# demo.net
KiCad netlist of a schematic drawn in EasyEDA Pro
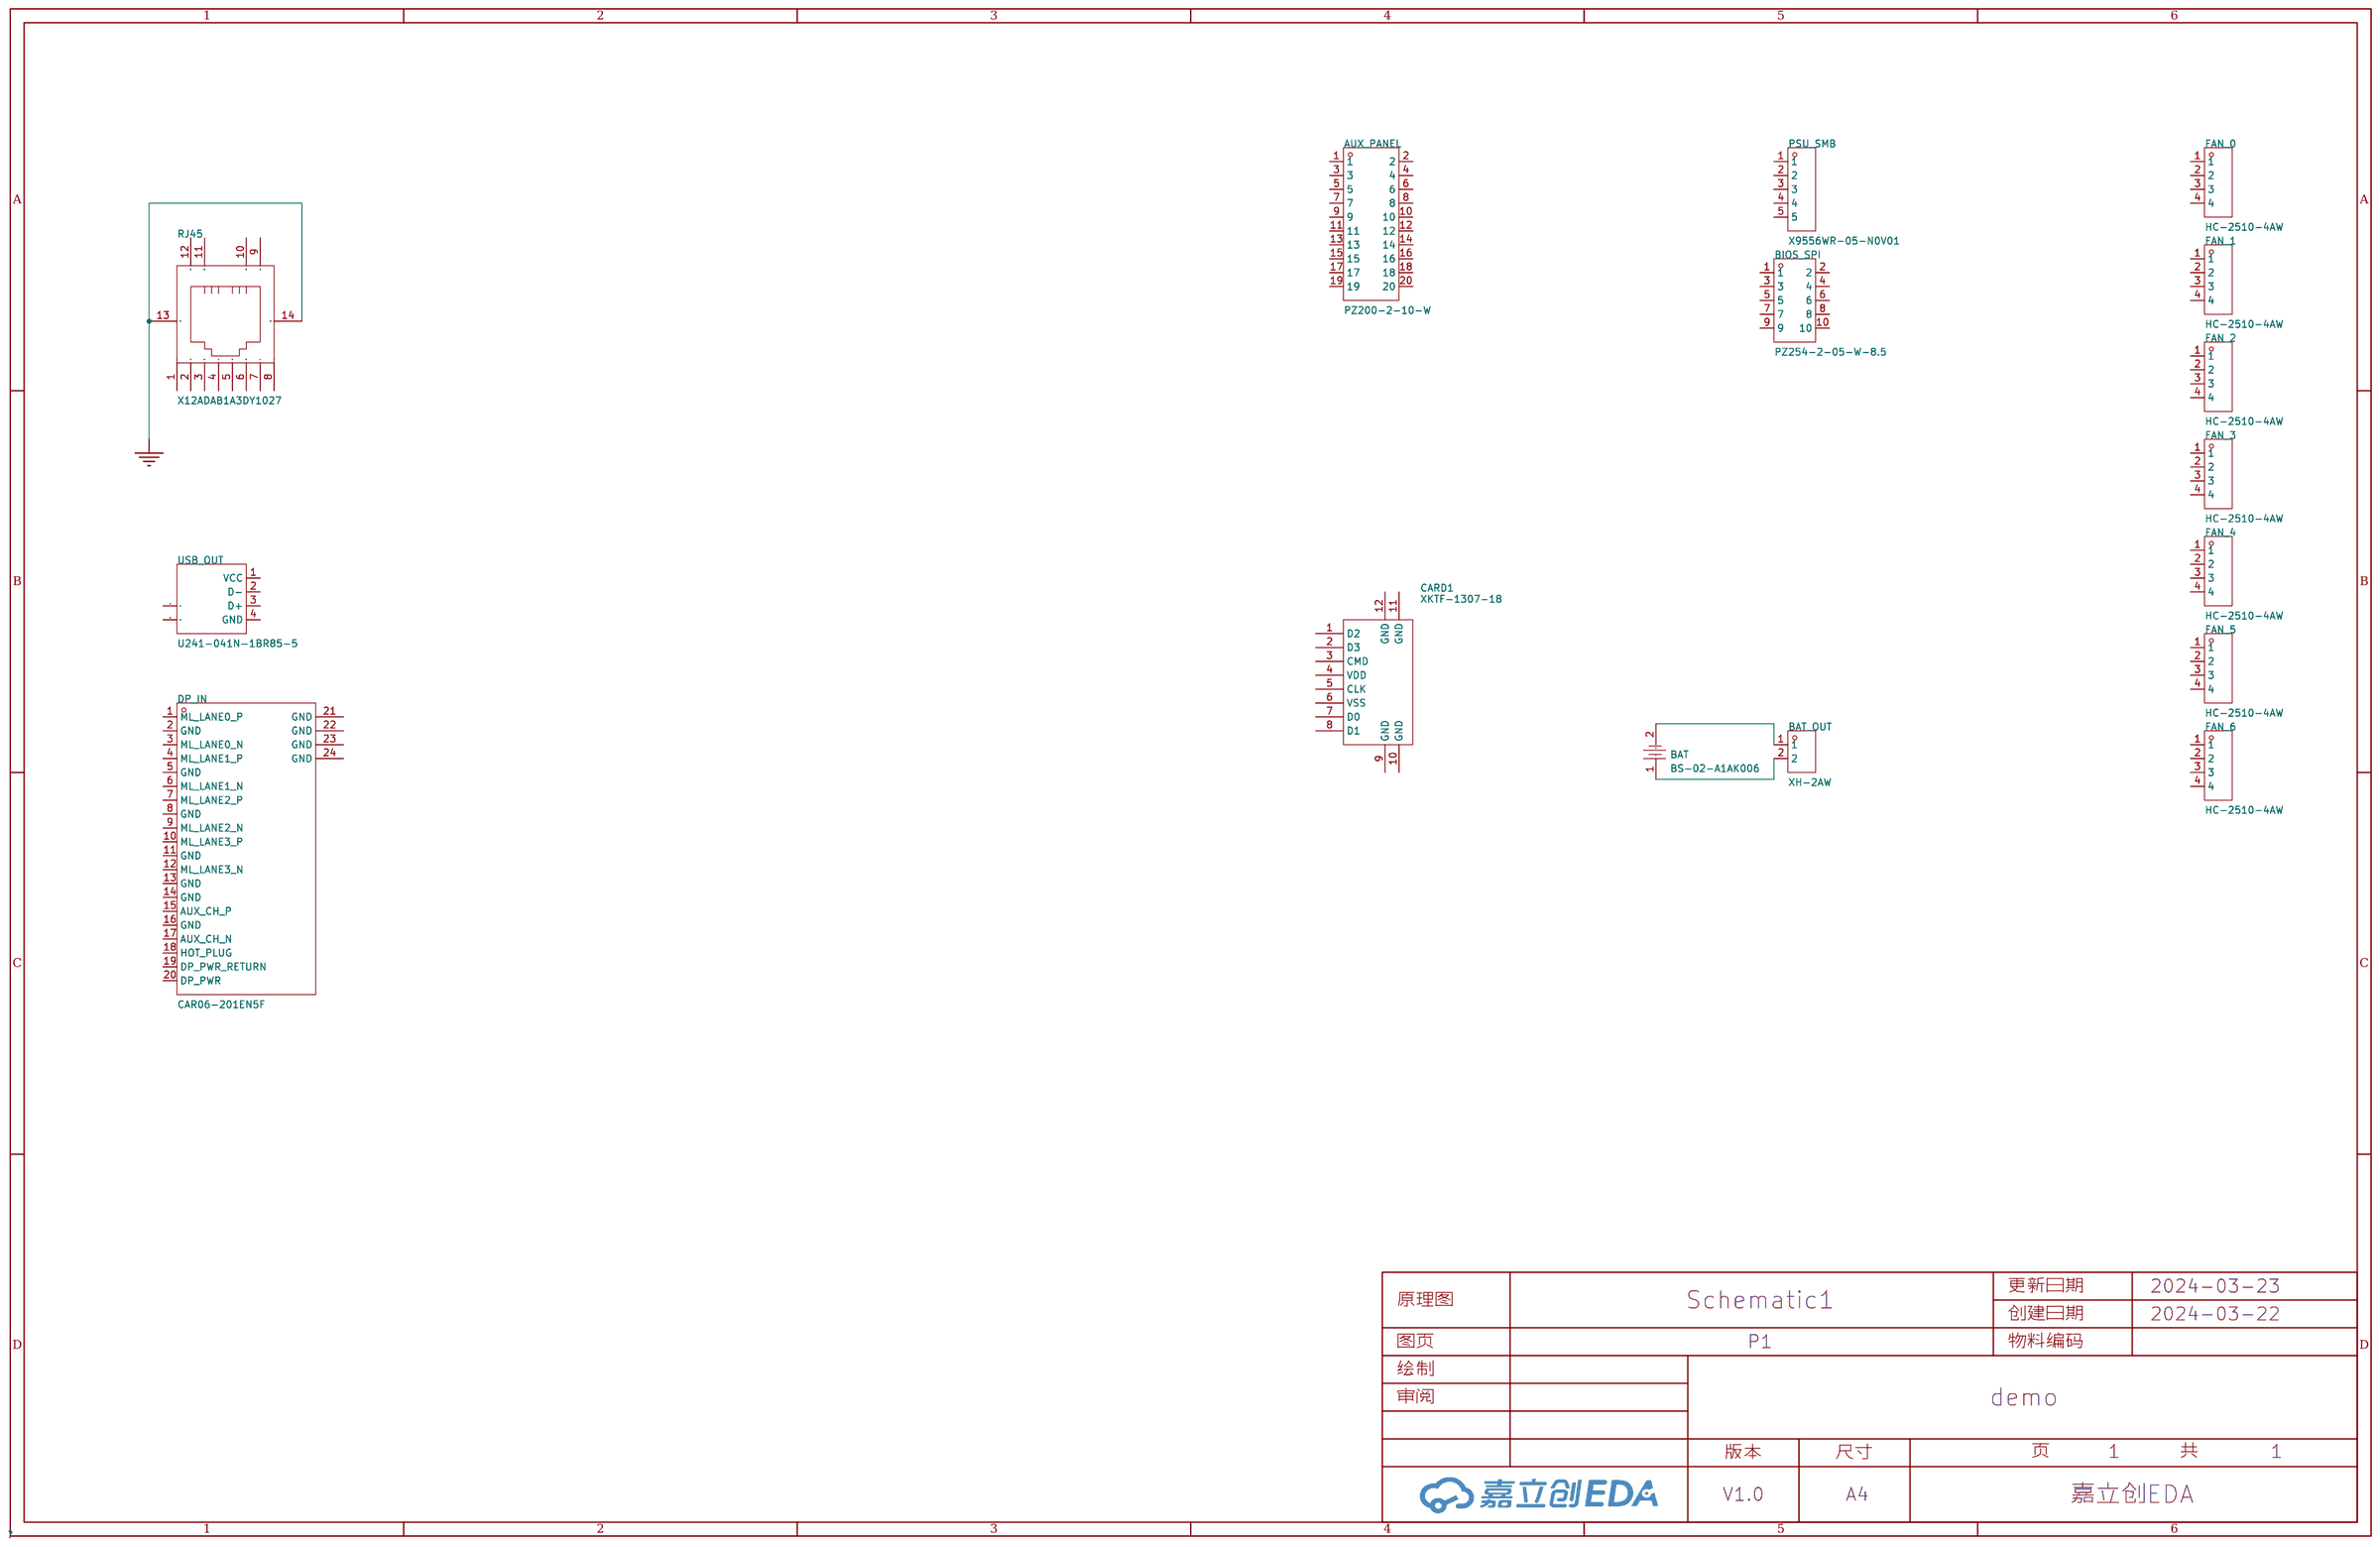
[diagram p0: schematic sheet]

(export (version "E")
  (design (tool "Eeschema 10.0.6"))
  (components
    (comp (ref "AUX_PANEL")
      (value "PZ200-2-10-W")
      (footprint "easyedapro:HDR-TH_20P-P2.00-H-M-R2-C10-S2.00-W9.4")
      (fields (field (name "Manufacturer") "HCTL(华灿天禄)"))
      (libsource (lib "easyedapro") (part "PZ200-2-10-W"))
    )
    (comp (ref "BAT")
      (value "BS-02-A1AK006")
      (footprint "easyedapro:BAT-TH_BS-02-A1AK006")
      (description "连接器类型:电池底座;适用电池规格:CR2032;触点电镀:锡;工作温度范围:-25°C~+85°C;")
      (fields (field (name "Manufacturer") "MYOUNG(美阳)"))
      (libsource (lib "easyedapro") (part "BS-02-A1AK006"))
    )
    (comp (ref "BAT_OUT")
      (value "XH-2AW")
      (footprint "easyedapro:CONN-TH_XH-2AW_C2908611")
      (fields (field (name "Manufacturer") "HCTL(华灿天禄)"))
      (libsource (lib "easyedapro") (part "XH-2AW_C2908611"))
    )
    (comp (ref "BIOS_SPI")
      (value "PZ254-2-05-W-8.5")
      (footprint "easyedapro:HDR-TH_10P-P2.54-H-M-R2-C5-S2.54-N")
      (fields (field (name "Manufacturer") "HCTL(华灿天禄)"))
      (libsource (lib "easyedapro") (part "PZ254-2-05-W-8.5"))
    )
    (comp (ref "CARD1")
      (value "XKTF-1307-18")
      (footprint "easyedapro:TF-SMD_XKTF-1307-18")
      (fields (field (name "Manufacturer") "XKB Connectivity(中国星坤)"))
      (libsource (lib "easyedapro") (part "XKTF-1307-18"))
    )
    (comp (ref "DP_IN")
      (value "CAR06-201EN5F")
      (footprint "easyedapro:DP-SMD_CAR06-201EN5F")
      (description "连接器类型:DisplayPort;公母:母;总PIN位数:20P;安装方式:卧贴;排数:1;额定电流:500mA;工作温度范围:-25°C~+85°C;")
      (fields (field (name "Manufacturer") "XKB Connectivity(中国星坤)"))
      (libsource (lib "easyedapro") (part "CAR06-201EN5F"))
    )
    (comp (ref "FAN_0")
      (value "HC-2510-4AW")
      (footprint "easyedapro:CONN-TH_4P-P2.54_HCTL_HC-2510-4AW")
      (fields (field (name "Manufacturer") "HCTL(华灿天禄)"))
      (libsource (lib "easyedapro") (part "HC-2510-4AW"))
    )
    (comp (ref "FAN_1")
      (value "HC-2510-4AW")
      (footprint "easyedapro:CONN-TH_4P-P2.54_HCTL_HC-2510-4AW")
      (fields (field (name "Manufacturer") "HCTL(华灿天禄)"))
      (libsource (lib "easyedapro") (part "HC-2510-4AW"))
    )
    (comp (ref "FAN_2")
      (value "HC-2510-4AW")
      (footprint "easyedapro:CONN-TH_4P-P2.54_HCTL_HC-2510-4AW")
      (fields (field (name "Manufacturer") "HCTL(华灿天禄)"))
      (libsource (lib "easyedapro") (part "HC-2510-4AW"))
    )
    (comp (ref "FAN_3")
      (value "HC-2510-4AW")
      (footprint "easyedapro:CONN-TH_4P-P2.54_HCTL_HC-2510-4AW")
      (fields (field (name "Manufacturer") "HCTL(华灿天禄)"))
      (libsource (lib "easyedapro") (part "HC-2510-4AW"))
    )
    (comp (ref "FAN_4")
      (value "HC-2510-4AW")
      (footprint "easyedapro:CONN-TH_4P-P2.54_HCTL_HC-2510-4AW")
      (fields (field (name "Manufacturer") "HCTL(华灿天禄)"))
      (libsource (lib "easyedapro") (part "HC-2510-4AW"))
    )
    (comp (ref "FAN_5")
      (value "HC-2510-4AW")
      (footprint "easyedapro:CONN-TH_4P-P2.54_HCTL_HC-2510-4AW")
      (fields (field (name "Manufacturer") "HCTL(华灿天禄)"))
      (libsource (lib "easyedapro") (part "HC-2510-4AW"))
    )
    (comp (ref "FAN_6")
      (value "HC-2510-4AW")
      (footprint "easyedapro:CONN-TH_4P-P2.54_HCTL_HC-2510-4AW")
      (fields (field (name "Manufacturer") "HCTL(华灿天禄)"))
      (libsource (lib "easyedapro") (part "HC-2510-4AW"))
    )
    (comp (ref "PSU_SMB")
      (value "X9556WR-05-N0V01")
      (footprint "easyedapro:CONN-TH_5P-P2.54_X9556WR-05-N0V01")
      (fields (field (name "Manufacturer") "XKB Connectivity(中国星坤)"))
      (libsource (lib "easyedapro") (part "X9556WR-05-N0V01"))
    )
    (comp (ref "RJ45")
      (value "X12ADAB1A3DY1027")
      (footprint "easyedapro:RJ45-TH_XKB_X12ADAB1A3DY1027")
      (fields (field (name "Manufacturer") "XKB Connectivity(中国星坤)"))
      (libsource (lib "easyedapro") (part "X12ADAB1A3DY1027"))
    )
    (comp (ref "USB_OUT")
      (value "U241-041N-1BR85-5")
      (footprint "easyedapro:USB-B-TH_U241-041N-1BR85-1")
      (fields (field (name "Manufacturer") "XKB Connectivity(中国星坤)"))
      (libsource (lib "easyedapro") (part "U241-041N-1BR85-5"))
    )
  )
  (nets
    (net (code "1") (name "GND") (class "Default")
      (node (ref "RJ45") (pin "13") (pinfunction "GND_13") (pintype "unspecified"))
      (node (ref "RJ45") (pin "14") (pinfunction "GND_14") (pintype "unspecified"))
    )
    (net (code "2") (name "Net-(BAT-Pad1)") (class "Default")
      (node (ref "BAT") (pin "1") (pinfunction "1_1") (pintype "input"))
      (node (ref "BAT_OUT") (pin "2") (pinfunction "2_2") (pintype "unspecified"))
    )
    (net (code "3") (name "Net-(BAT-Pad2)") (class "Default")
      (node (ref "BAT") (pin "2") (pinfunction "2_2") (pintype "input"))
      (node (ref "BAT_OUT") (pin "1") (pinfunction "1_1") (pintype "unspecified"))
    )
    (net (code "4") (name "unconnected-(AUX_PANEL-Pad1)") (class "Default")
      (node (ref "AUX_PANEL") (pin "1") (pinfunction "1_1") (pintype "unspecified"))
    )
    (net (code "5") (name "unconnected-(AUX_PANEL-Pad2)") (class "Default")
      (node (ref "AUX_PANEL") (pin "2") (pinfunction "2_2") (pintype "unspecified"))
    )
    (net (code "6") (name "unconnected-(AUX_PANEL-Pad3)") (class "Default")
      (node (ref "AUX_PANEL") (pin "3") (pinfunction "3_3") (pintype "unspecified"))
    )
    (net (code "7") (name "unconnected-(AUX_PANEL-Pad4)") (class "Default")
      (node (ref "AUX_PANEL") (pin "4") (pinfunction "4_4") (pintype "unspecified"))
    )
    (net (code "8") (name "unconnected-(AUX_PANEL-Pad5)") (class "Default")
      (node (ref "AUX_PANEL") (pin "5") (pinfunction "5_5") (pintype "unspecified"))
    )
    (net (code "9") (name "unconnected-(AUX_PANEL-Pad6)") (class "Default")
      (node (ref "AUX_PANEL") (pin "6") (pinfunction "6_6") (pintype "unspecified"))
    )
    (net (code "10") (name "unconnected-(AUX_PANEL-Pad7)") (class "Default")
      (node (ref "AUX_PANEL") (pin "7") (pinfunction "7_7") (pintype "unspecified"))
    )
    (net (code "11") (name "unconnected-(AUX_PANEL-Pad8)") (class "Default")
      (node (ref "AUX_PANEL") (pin "8") (pinfunction "8_8") (pintype "unspecified"))
    )
    (net (code "12") (name "unconnected-(AUX_PANEL-Pad9)") (class "Default")
      (node (ref "AUX_PANEL") (pin "9") (pinfunction "9_9") (pintype "unspecified"))
    )
    (net (code "13") (name "unconnected-(AUX_PANEL-Pad10)") (class "Default")
      (node (ref "AUX_PANEL") (pin "10") (pinfunction "10_10") (pintype "unspecified"))
    )
    (net (code "14") (name "unconnected-(AUX_PANEL-Pad11)") (class "Default")
      (node (ref "AUX_PANEL") (pin "11") (pinfunction "11_11") (pintype "unspecified"))
    )
    (net (code "15") (name "unconnected-(AUX_PANEL-Pad12)") (class "Default")
      (node (ref "AUX_PANEL") (pin "12") (pinfunction "12_12") (pintype "unspecified"))
    )
    (net (code "16") (name "unconnected-(AUX_PANEL-Pad13)") (class "Default")
      (node (ref "AUX_PANEL") (pin "13") (pinfunction "13_13") (pintype "unspecified"))
    )
    (net (code "17") (name "unconnected-(AUX_PANEL-Pad14)") (class "Default")
      (node (ref "AUX_PANEL") (pin "14") (pinfunction "14_14") (pintype "unspecified"))
    )
    (net (code "18") (name "unconnected-(AUX_PANEL-Pad15)") (class "Default")
      (node (ref "AUX_PANEL") (pin "15") (pinfunction "15_15") (pintype "unspecified"))
    )
    (net (code "19") (name "unconnected-(AUX_PANEL-Pad16)") (class "Default")
      (node (ref "AUX_PANEL") (pin "16") (pinfunction "16_16") (pintype "unspecified"))
    )
    (net (code "20") (name "unconnected-(AUX_PANEL-Pad17)") (class "Default")
      (node (ref "AUX_PANEL") (pin "17") (pinfunction "17_17") (pintype "unspecified"))
    )
    (net (code "21") (name "unconnected-(AUX_PANEL-Pad18)") (class "Default")
      (node (ref "AUX_PANEL") (pin "18") (pinfunction "18_18") (pintype "unspecified"))
    )
    (net (code "22") (name "unconnected-(AUX_PANEL-Pad19)") (class "Default")
      (node (ref "AUX_PANEL") (pin "19") (pinfunction "19_19") (pintype "unspecified"))
    )
    (net (code "23") (name "unconnected-(AUX_PANEL-Pad20)") (class "Default")
      (node (ref "AUX_PANEL") (pin "20") (pinfunction "20_20") (pintype "unspecified"))
    )
    (net (code "24") (name "unconnected-(BIOS_SPI-Pad1)") (class "Default")
      (node (ref "BIOS_SPI") (pin "1") (pinfunction "1_1") (pintype "unspecified"))
    )
    (net (code "25") (name "unconnected-(BIOS_SPI-Pad2)") (class "Default")
      (node (ref "BIOS_SPI") (pin "2") (pinfunction "2_2") (pintype "unspecified"))
    )
    (net (code "26") (name "unconnected-(BIOS_SPI-Pad3)") (class "Default")
      (node (ref "BIOS_SPI") (pin "3") (pinfunction "3_3") (pintype "unspecified"))
    )
    (net (code "27") (name "unconnected-(BIOS_SPI-Pad4)") (class "Default")
      (node (ref "BIOS_SPI") (pin "4") (pinfunction "4_4") (pintype "unspecified"))
    )
    (net (code "28") (name "unconnected-(BIOS_SPI-Pad5)") (class "Default")
      (node (ref "BIOS_SPI") (pin "5") (pinfunction "5_5") (pintype "unspecified"))
    )
    (net (code "29") (name "unconnected-(BIOS_SPI-Pad6)") (class "Default")
      (node (ref "BIOS_SPI") (pin "6") (pinfunction "6_6") (pintype "unspecified"))
    )
    (net (code "30") (name "unconnected-(BIOS_SPI-Pad7)") (class "Default")
      (node (ref "BIOS_SPI") (pin "7") (pinfunction "7_7") (pintype "unspecified"))
    )
    (net (code "31") (name "unconnected-(BIOS_SPI-Pad8)") (class "Default")
      (node (ref "BIOS_SPI") (pin "8") (pinfunction "8_8") (pintype "unspecified"))
    )
    (net (code "32") (name "unconnected-(BIOS_SPI-Pad9)") (class "Default")
      (node (ref "BIOS_SPI") (pin "9") (pinfunction "9_9") (pintype "unspecified"))
    )
    (net (code "33") (name "unconnected-(BIOS_SPI-Pad10)") (class "Default")
      (node (ref "BIOS_SPI") (pin "10") (pinfunction "10_10") (pintype "unspecified"))
    )
    (net (code "34") (name "unconnected-(CARD1-CLK-Pad5)") (class "Default")
      (node (ref "CARD1") (pin "5") (pinfunction "CLK_5") (pintype "input"))
    )
    (net (code "35") (name "unconnected-(CARD1-CMD-Pad3)") (class "Default")
      (node (ref "CARD1") (pin "3") (pinfunction "CMD_3") (pintype "input"))
    )
    (net (code "36") (name "unconnected-(CARD1-D0-Pad7)") (class "Default")
      (node (ref "CARD1") (pin "7") (pinfunction "D0_7") (pintype "input"))
    )
    (net (code "37") (name "unconnected-(CARD1-D1-Pad8)") (class "Default")
      (node (ref "CARD1") (pin "8") (pinfunction "D1_8") (pintype "input"))
    )
    (net (code "38") (name "unconnected-(CARD1-D2-Pad1)") (class "Default")
      (node (ref "CARD1") (pin "1") (pinfunction "D2_1") (pintype "input"))
    )
    (net (code "39") (name "unconnected-(CARD1-D3-Pad2)") (class "Default")
      (node (ref "CARD1") (pin "2") (pinfunction "D3_2") (pintype "input"))
    )
    (net (code "40") (name "unconnected-(CARD1-GND-Pad9)") (class "Default")
      (node (ref "CARD1") (pin "9") (pinfunction "GND_9") (pintype "input"))
    )
    (net (code "41") (name "unconnected-(CARD1-GND-Pad10)") (class "Default")
      (node (ref "CARD1") (pin "10") (pinfunction "GND_10") (pintype "input"))
    )
    (net (code "42") (name "unconnected-(CARD1-GND-Pad11)") (class "Default")
      (node (ref "CARD1") (pin "11") (pinfunction "GND_11") (pintype "input"))
    )
    (net (code "43") (name "unconnected-(CARD1-GND-Pad12)") (class "Default")
      (node (ref "CARD1") (pin "12") (pinfunction "GND_12") (pintype "input"))
    )
    (net (code "44") (name "unconnected-(CARD1-VDD-Pad4)") (class "Default")
      (node (ref "CARD1") (pin "4") (pinfunction "VDD_4") (pintype "input"))
    )
    (net (code "45") (name "unconnected-(CARD1-VSS-Pad6)") (class "Default")
      (node (ref "CARD1") (pin "6") (pinfunction "VSS_6") (pintype "input"))
    )
    (net (code "46") (name "unconnected-(DP_IN-AUX_CH_N-Pad17)") (class "Default")
      (node (ref "DP_IN") (pin "17") (pinfunction "AUX_CH_N_17") (pintype "unspecified"))
    )
    (net (code "47") (name "unconnected-(DP_IN-AUX_CH_P-Pad15)") (class "Default")
      (node (ref "DP_IN") (pin "15") (pinfunction "AUX_CH_P_15") (pintype "unspecified"))
    )
    (net (code "48") (name "unconnected-(DP_IN-DP_PWR-Pad20)") (class "Default")
      (node (ref "DP_IN") (pin "20") (pinfunction "DP_PWR_20") (pintype "unspecified"))
    )
    (net (code "49") (name "unconnected-(DP_IN-DP_PWR_RETURN-Pad19)") (class "Default")
      (node (ref "DP_IN") (pin "19") (pinfunction "DP_PWR_RETURN_19") (pintype "unspecified"))
    )
    (net (code "50") (name "unconnected-(DP_IN-GND-Pad2)") (class "Default")
      (node (ref "DP_IN") (pin "2") (pinfunction "GND_2") (pintype "unspecified"))
    )
    (net (code "51") (name "unconnected-(DP_IN-GND-Pad5)") (class "Default")
      (node (ref "DP_IN") (pin "5") (pinfunction "GND_5") (pintype "unspecified"))
    )
    (net (code "52") (name "unconnected-(DP_IN-GND-Pad8)") (class "Default")
      (node (ref "DP_IN") (pin "8") (pinfunction "GND_8") (pintype "unspecified"))
    )
    (net (code "53") (name "unconnected-(DP_IN-GND-Pad11)") (class "Default")
      (node (ref "DP_IN") (pin "11") (pinfunction "GND_11") (pintype "unspecified"))
    )
    (net (code "54") (name "unconnected-(DP_IN-GND-Pad13)") (class "Default")
      (node (ref "DP_IN") (pin "13") (pinfunction "GND_13") (pintype "unspecified"))
    )
    (net (code "55") (name "unconnected-(DP_IN-GND-Pad14)") (class "Default")
      (node (ref "DP_IN") (pin "14") (pinfunction "GND_14") (pintype "unspecified"))
    )
    (net (code "56") (name "unconnected-(DP_IN-GND-Pad16)") (class "Default")
      (node (ref "DP_IN") (pin "16") (pinfunction "GND_16") (pintype "unspecified"))
    )
    (net (code "57") (name "unconnected-(DP_IN-GND-Pad21)") (class "Default")
      (node (ref "DP_IN") (pin "21") (pinfunction "GND_21") (pintype "unspecified"))
    )
    (net (code "58") (name "unconnected-(DP_IN-GND-Pad22)") (class "Default")
      (node (ref "DP_IN") (pin "22") (pinfunction "GND_22") (pintype "unspecified"))
    )
    (net (code "59") (name "unconnected-(DP_IN-GND-Pad23)") (class "Default")
      (node (ref "DP_IN") (pin "23") (pinfunction "GND_23") (pintype "unspecified"))
    )
    (net (code "60") (name "unconnected-(DP_IN-GND-Pad24)") (class "Default")
      (node (ref "DP_IN") (pin "24") (pinfunction "GND_24") (pintype "unspecified"))
    )
    (net (code "61") (name "unconnected-(DP_IN-HOT_PLUG-Pad18)") (class "Default")
      (node (ref "DP_IN") (pin "18") (pinfunction "HOT_PLUG_18") (pintype "unspecified"))
    )
    (net (code "62") (name "unconnected-(DP_IN-ML_LANE0_N-Pad3)") (class "Default")
      (node (ref "DP_IN") (pin "3") (pinfunction "ML_LANE0_N_3") (pintype "unspecified"))
    )
    (net (code "63") (name "unconnected-(DP_IN-ML_LANE0_P-Pad1)") (class "Default")
      (node (ref "DP_IN") (pin "1") (pinfunction "ML_LANE0_P_1") (pintype "unspecified"))
    )
    (net (code "64") (name "unconnected-(DP_IN-ML_LANE1_N-Pad6)") (class "Default")
      (node (ref "DP_IN") (pin "6") (pinfunction "ML_LANE1_N_6") (pintype "unspecified"))
    )
    (net (code "65") (name "unconnected-(DP_IN-ML_LANE1_P-Pad4)") (class "Default")
      (node (ref "DP_IN") (pin "4") (pinfunction "ML_LANE1_P_4") (pintype "unspecified"))
    )
    (net (code "66") (name "unconnected-(DP_IN-ML_LANE2_N-Pad9)") (class "Default")
      (node (ref "DP_IN") (pin "9") (pinfunction "ML_LANE2_N_9") (pintype "unspecified"))
    )
    (net (code "67") (name "unconnected-(DP_IN-ML_LANE2_P-Pad7)") (class "Default")
      (node (ref "DP_IN") (pin "7") (pinfunction "ML_LANE2_P_7") (pintype "unspecified"))
    )
    (net (code "68") (name "unconnected-(DP_IN-ML_LANE3_N-Pad12)") (class "Default")
      (node (ref "DP_IN") (pin "12") (pinfunction "ML_LANE3_N_12") (pintype "unspecified"))
    )
    (net (code "69") (name "unconnected-(DP_IN-ML_LANE3_P-Pad10)") (class "Default")
      (node (ref "DP_IN") (pin "10") (pinfunction "ML_LANE3_P_10") (pintype "unspecified"))
    )
    (net (code "70") (name "unconnected-(FAN_0-Pad1)") (class "Default")
      (node (ref "FAN_0") (pin "1") (pinfunction "1_1") (pintype "unspecified"))
    )
    (net (code "71") (name "unconnected-(FAN_0-Pad2)") (class "Default")
      (node (ref "FAN_0") (pin "2") (pinfunction "2_2") (pintype "unspecified"))
    )
    (net (code "72") (name "unconnected-(FAN_0-Pad3)") (class "Default")
      (node (ref "FAN_0") (pin "3") (pinfunction "3_3") (pintype "unspecified"))
    )
    (net (code "73") (name "unconnected-(FAN_0-Pad4)") (class "Default")
      (node (ref "FAN_0") (pin "4") (pinfunction "4_4") (pintype "unspecified"))
    )
    (net (code "74") (name "unconnected-(FAN_1-Pad1)") (class "Default")
      (node (ref "FAN_1") (pin "1") (pinfunction "1_1") (pintype "unspecified"))
    )
    (net (code "75") (name "unconnected-(FAN_1-Pad2)") (class "Default")
      (node (ref "FAN_1") (pin "2") (pinfunction "2_2") (pintype "unspecified"))
    )
    (net (code "76") (name "unconnected-(FAN_1-Pad3)") (class "Default")
      (node (ref "FAN_1") (pin "3") (pinfunction "3_3") (pintype "unspecified"))
    )
    (net (code "77") (name "unconnected-(FAN_1-Pad4)") (class "Default")
      (node (ref "FAN_1") (pin "4") (pinfunction "4_4") (pintype "unspecified"))
    )
    (net (code "78") (name "unconnected-(FAN_2-Pad1)") (class "Default")
      (node (ref "FAN_2") (pin "1") (pinfunction "1_1") (pintype "unspecified"))
    )
    (net (code "79") (name "unconnected-(FAN_2-Pad2)") (class "Default")
      (node (ref "FAN_2") (pin "2") (pinfunction "2_2") (pintype "unspecified"))
    )
    (net (code "80") (name "unconnected-(FAN_2-Pad3)") (class "Default")
      (node (ref "FAN_2") (pin "3") (pinfunction "3_3") (pintype "unspecified"))
    )
    (net (code "81") (name "unconnected-(FAN_2-Pad4)") (class "Default")
      (node (ref "FAN_2") (pin "4") (pinfunction "4_4") (pintype "unspecified"))
    )
    (net (code "82") (name "unconnected-(FAN_3-Pad1)") (class "Default")
      (node (ref "FAN_3") (pin "1") (pinfunction "1_1") (pintype "unspecified"))
    )
    (net (code "83") (name "unconnected-(FAN_3-Pad2)") (class "Default")
      (node (ref "FAN_3") (pin "2") (pinfunction "2_2") (pintype "unspecified"))
    )
    (net (code "84") (name "unconnected-(FAN_3-Pad3)") (class "Default")
      (node (ref "FAN_3") (pin "3") (pinfunction "3_3") (pintype "unspecified"))
    )
    (net (code "85") (name "unconnected-(FAN_3-Pad4)") (class "Default")
      (node (ref "FAN_3") (pin "4") (pinfunction "4_4") (pintype "unspecified"))
    )
    (net (code "86") (name "unconnected-(FAN_4-Pad1)") (class "Default")
      (node (ref "FAN_4") (pin "1") (pinfunction "1_1") (pintype "unspecified"))
    )
    (net (code "87") (name "unconnected-(FAN_4-Pad2)") (class "Default")
      (node (ref "FAN_4") (pin "2") (pinfunction "2_2") (pintype "unspecified"))
    )
    (net (code "88") (name "unconnected-(FAN_4-Pad3)") (class "Default")
      (node (ref "FAN_4") (pin "3") (pinfunction "3_3") (pintype "unspecified"))
    )
    (net (code "89") (name "unconnected-(FAN_4-Pad4)") (class "Default")
      (node (ref "FAN_4") (pin "4") (pinfunction "4_4") (pintype "unspecified"))
    )
    (net (code "90") (name "unconnected-(FAN_5-Pad1)") (class "Default")
      (node (ref "FAN_5") (pin "1") (pinfunction "1_1") (pintype "unspecified"))
    )
    (net (code "91") (name "unconnected-(FAN_5-Pad2)") (class "Default")
      (node (ref "FAN_5") (pin "2") (pinfunction "2_2") (pintype "unspecified"))
    )
    (net (code "92") (name "unconnected-(FAN_5-Pad3)") (class "Default")
      (node (ref "FAN_5") (pin "3") (pinfunction "3_3") (pintype "unspecified"))
    )
    (net (code "93") (name "unconnected-(FAN_5-Pad4)") (class "Default")
      (node (ref "FAN_5") (pin "4") (pinfunction "4_4") (pintype "unspecified"))
    )
    (net (code "94") (name "unconnected-(FAN_6-Pad1)") (class "Default")
      (node (ref "FAN_6") (pin "1") (pinfunction "1_1") (pintype "unspecified"))
    )
    (net (code "95") (name "unconnected-(FAN_6-Pad2)") (class "Default")
      (node (ref "FAN_6") (pin "2") (pinfunction "2_2") (pintype "unspecified"))
    )
    (net (code "96") (name "unconnected-(FAN_6-Pad3)") (class "Default")
      (node (ref "FAN_6") (pin "3") (pinfunction "3_3") (pintype "unspecified"))
    )
    (net (code "97") (name "unconnected-(FAN_6-Pad4)") (class "Default")
      (node (ref "FAN_6") (pin "4") (pinfunction "4_4") (pintype "unspecified"))
    )
    (net (code "98") (name "unconnected-(PSU_SMB-Pad1)") (class "Default")
      (node (ref "PSU_SMB") (pin "1") (pinfunction "1_1") (pintype "unspecified"))
    )
    (net (code "99") (name "unconnected-(PSU_SMB-Pad2)") (class "Default")
      (node (ref "PSU_SMB") (pin "2") (pinfunction "2_2") (pintype "unspecified"))
    )
    (net (code "100") (name "unconnected-(PSU_SMB-Pad3)") (class "Default")
      (node (ref "PSU_SMB") (pin "3") (pinfunction "3_3") (pintype "unspecified"))
    )
    (net (code "101") (name "unconnected-(PSU_SMB-Pad4)") (class "Default")
      (node (ref "PSU_SMB") (pin "4") (pinfunction "4_4") (pintype "unspecified"))
    )
    (net (code "102") (name "unconnected-(PSU_SMB-Pad5)") (class "Default")
      (node (ref "PSU_SMB") (pin "5") (pinfunction "5_5") (pintype "unspecified"))
    )
    (net (code "103") (name "unconnected-(RJ45-LEDG+-Pad10)") (class "Default")
      (node (ref "RJ45") (pin "10") (pinfunction "LEDG+_10") (pintype "unspecified"))
    )
    (net (code "104") (name "unconnected-(RJ45-LEDG--Pad9)") (class "Default")
      (node (ref "RJ45") (pin "9") (pinfunction "LEDG-_9") (pintype "unspecified"))
    )
    (net (code "105") (name "unconnected-(RJ45-LEDY+-Pad12)") (class "Default")
      (node (ref "RJ45") (pin "12") (pinfunction "LEDY+_12") (pintype "unspecified"))
    )
    (net (code "106") (name "unconnected-(RJ45-LEDY--Pad11)") (class "Default")
      (node (ref "RJ45") (pin "11") (pinfunction "LEDY-_11") (pintype "unspecified"))
    )
    (net (code "107") (name "unconnected-(RJ45-Pad1)") (class "Default")
      (node (ref "RJ45") (pin "1") (pinfunction "1_1") (pintype "unspecified"))
    )
    (net (code "108") (name "unconnected-(RJ45-Pad2)") (class "Default")
      (node (ref "RJ45") (pin "2") (pinfunction "2_2") (pintype "unspecified"))
    )
    (net (code "109") (name "unconnected-(RJ45-Pad3)") (class "Default")
      (node (ref "RJ45") (pin "3") (pinfunction "3_3") (pintype "unspecified"))
    )
    (net (code "110") (name "unconnected-(RJ45-Pad4)") (class "Default")
      (node (ref "RJ45") (pin "4") (pinfunction "4_4") (pintype "unspecified"))
    )
    (net (code "111") (name "unconnected-(RJ45-Pad5)") (class "Default")
      (node (ref "RJ45") (pin "5") (pinfunction "5_5") (pintype "unspecified"))
    )
    (net (code "112") (name "unconnected-(RJ45-Pad6)") (class "Default")
      (node (ref "RJ45") (pin "6") (pinfunction "6_6") (pintype "unspecified"))
    )
    (net (code "113") (name "unconnected-(RJ45-Pad7)") (class "Default")
      (node (ref "RJ45") (pin "7") (pinfunction "7_7") (pintype "unspecified"))
    )
    (net (code "114") (name "unconnected-(RJ45-Pad8)") (class "Default")
      (node (ref "RJ45") (pin "8") (pinfunction "8_8") (pintype "unspecified"))
    )
    (net (code "115") (name "unconnected-(USB_OUT-D+-Pad3)") (class "Default")
      (node (ref "USB_OUT") (pin "3") (pinfunction "D+_3") (pintype "input"))
    )
    (net (code "116") (name "unconnected-(USB_OUT-D--Pad2)") (class "Default")
      (node (ref "USB_OUT") (pin "2") (pinfunction "D-_2") (pintype "input"))
    )
    (net (code "117") (name "unconnected-(USB_OUT-GND-Pad4)") (class "Default")
      (node (ref "USB_OUT") (pin "4") (pinfunction "GND_4") (pintype "input"))
    )
    (net (code "118") (name "unconnected-(USB_OUT-Pad5)") (class "Default")
      (node (ref "USB_OUT") (pin "5") (pinfunction "5_5") (pintype "unspecified"))
    )
    (net (code "119") (name "unconnected-(USB_OUT-Pad6)") (class "Default")
      (node (ref "USB_OUT") (pin "6") (pinfunction "6_6") (pintype "unspecified"))
    )
    (net (code "120") (name "unconnected-(USB_OUT-VCC-Pad1)") (class "Default")
      (node (ref "USB_OUT") (pin "1") (pinfunction "VCC_1") (pintype "input"))
    )
  )
)
